# Octaplexerv6_1.net
KiCad netlist of a schematic drawn in EAGLE
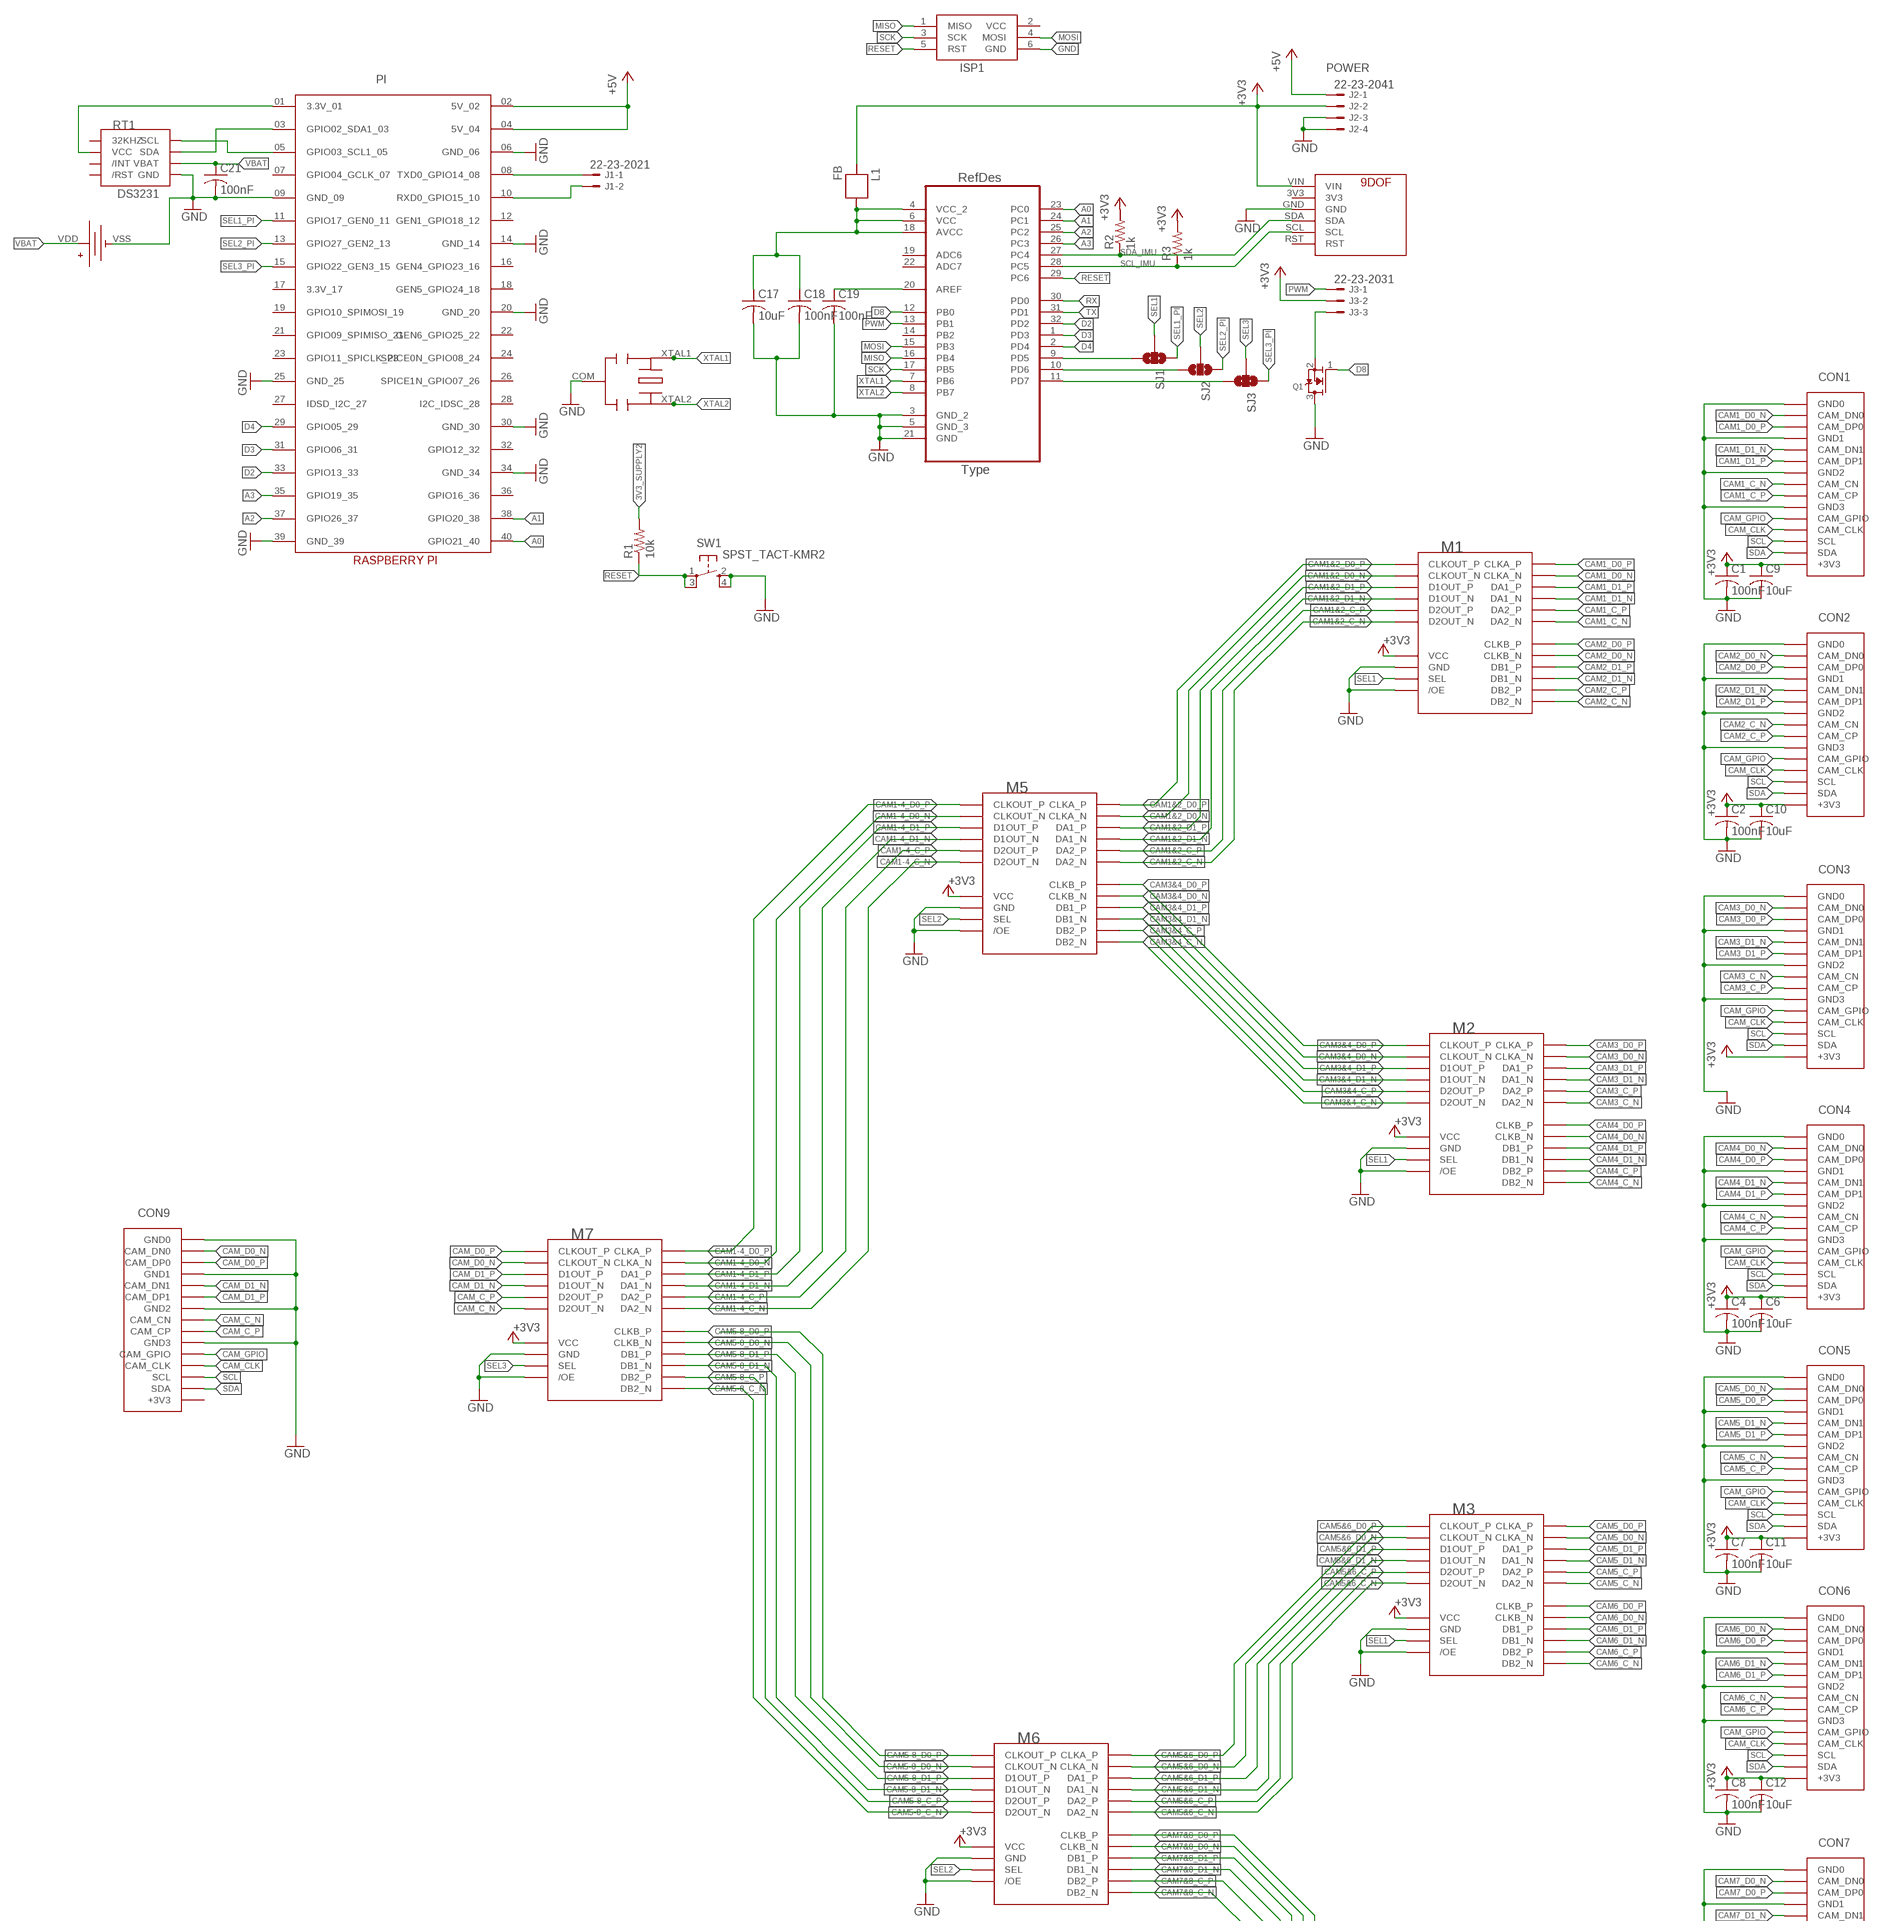
[diagram p0: schematic, sheet 1, part 1 of 2]
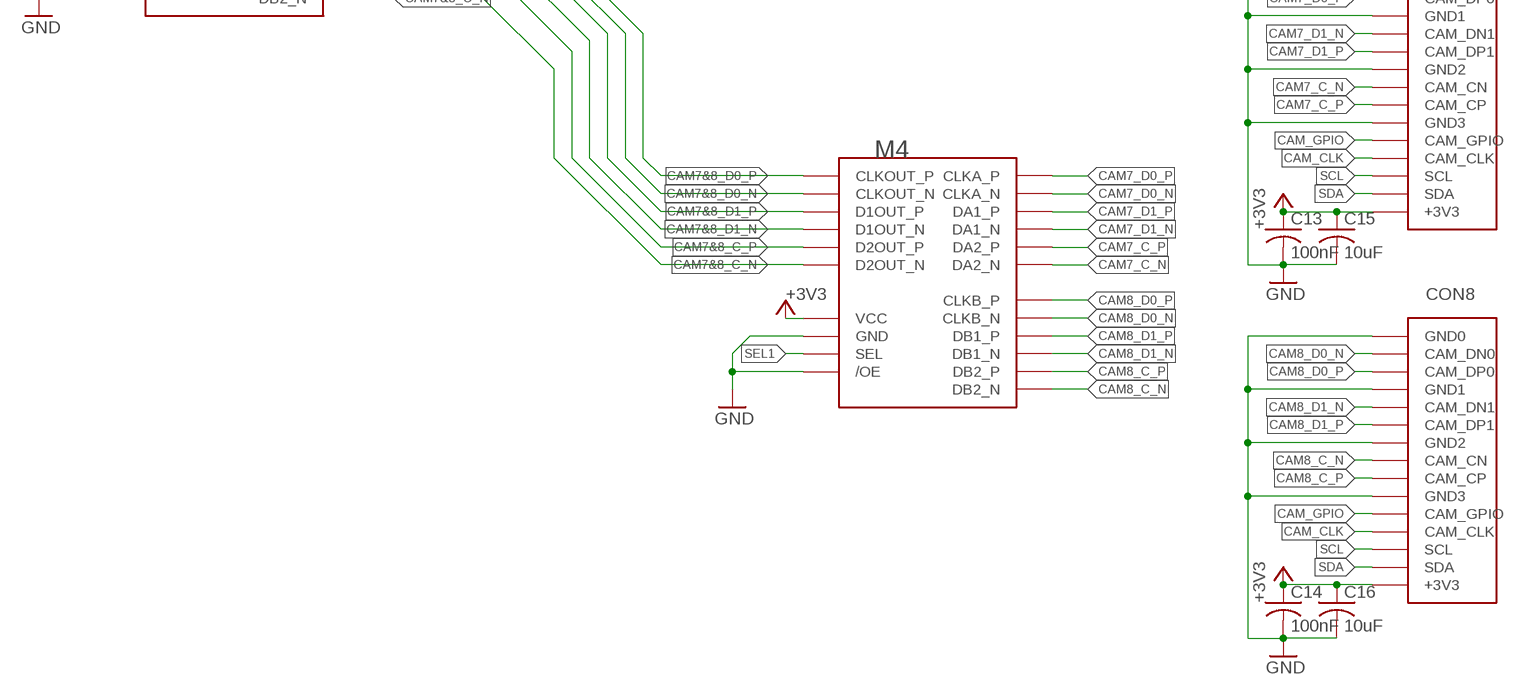
[diagram p1: schematic, sheet 1, part 2 of 2]

(export (version "E")
  (design (tool "Eeschema 10.0.6"))
  (components
    (comp (ref "C1")
      (value "100nF")
      (footprint "eagle-import:C0603")
      (libsource (lib "eagle-import") (part "C-USC0603"))
    )
    (comp (ref "C2")
      (value "100nF")
      (footprint "eagle-import:C0603")
      (libsource (lib "eagle-import") (part "C-USC0603"))
    )
    (comp (ref "C4")
      (value "100nF")
      (footprint "eagle-import:C0603")
      (libsource (lib "eagle-import") (part "C-USC0603"))
    )
    (comp (ref "C6")
      (value "10uF")
      (footprint "eagle-import:C0603")
      (libsource (lib "eagle-import") (part "C-USC0603"))
    )
    (comp (ref "C7")
      (value "100nF")
      (footprint "eagle-import:C0603")
      (libsource (lib "eagle-import") (part "C-USC0603"))
    )
    (comp (ref "C8")
      (value "100nF")
      (footprint "eagle-import:C0603")
      (libsource (lib "eagle-import") (part "C-USC0603"))
    )
    (comp (ref "C9")
      (value "10uF")
      (footprint "eagle-import:C0603")
      (libsource (lib "eagle-import") (part "C-USC0603"))
    )
    (comp (ref "C10")
      (value "10uF")
      (footprint "eagle-import:C0603")
      (libsource (lib "eagle-import") (part "C-USC0603"))
    )
    (comp (ref "C11")
      (value "10uF")
      (footprint "eagle-import:C0603")
      (libsource (lib "eagle-import") (part "C-USC0603"))
    )
    (comp (ref "C12")
      (value "10uF")
      (footprint "eagle-import:C0603")
      (libsource (lib "eagle-import") (part "C-USC0603"))
    )
    (comp (ref "C13")
      (value "100nF")
      (footprint "eagle-import:C0603")
      (libsource (lib "eagle-import") (part "C-USC0603"))
    )
    (comp (ref "C14")
      (value "100nF")
      (footprint "eagle-import:C0603")
      (libsource (lib "eagle-import") (part "C-USC0603"))
    )
    (comp (ref "C15")
      (value "10uF")
      (footprint "eagle-import:C0603")
      (libsource (lib "eagle-import") (part "C-USC0603"))
    )
    (comp (ref "C16")
      (value "10uF")
      (footprint "eagle-import:C0603")
      (libsource (lib "eagle-import") (part "C-USC0603"))
    )
    (comp (ref "C17")
      (value "10uF")
      (footprint "eagle-import:C0603")
      (libsource (lib "eagle-import") (part "C-USC0603"))
    )
    (comp (ref "C18")
      (value "100nF")
      (footprint "eagle-import:C0603")
      (libsource (lib "eagle-import") (part "C-USC0603"))
    )
    (comp (ref "C19")
      (value "100nF")
      (footprint "eagle-import:C0603")
      (libsource (lib "eagle-import") (part "C-USC0603"))
    )
    (comp (ref "C21")
      (value "100nF")
      (footprint "eagle-import:C0603")
      (libsource (lib "eagle-import") (part "C-USC0603"))
    )
    (comp (ref "CON1")
      (value "SLW15S-1C7LF")
      (footprint "eagle-import:SLW15R-1C7LF")
      (libsource (lib "eagle-import") (part "SLW15S-1C7LF"))
    )
    (comp (ref "CON2")
      (value "SLW15S-1C7LF")
      (footprint "eagle-import:SLW15R-1C7LF")
      (libsource (lib "eagle-import") (part "SLW15S-1C7LF"))
    )
    (comp (ref "CON3")
      (value "SLW15S-1C7LF")
      (footprint "eagle-import:SLW15R-1C7LF")
      (libsource (lib "eagle-import") (part "SLW15S-1C7LF"))
    )
    (comp (ref "CON4")
      (value "SLW15S-1C7LF")
      (footprint "eagle-import:SLW15R-1C7LF")
      (libsource (lib "eagle-import") (part "SLW15S-1C7LF"))
    )
    (comp (ref "CON5")
      (value "SLW15S-1C7LF")
      (footprint "eagle-import:SLW15R-1C7LF")
      (libsource (lib "eagle-import") (part "SLW15S-1C7LF"))
    )
    (comp (ref "CON6")
      (value "SLW15S-1C7LF")
      (footprint "eagle-import:SLW15R-1C7LF")
      (libsource (lib "eagle-import") (part "SLW15S-1C7LF"))
    )
    (comp (ref "CON7")
      (value "SLW15S-1C7LF")
      (footprint "eagle-import:SLW15R-1C7LF")
      (libsource (lib "eagle-import") (part "SLW15S-1C7LF"))
    )
    (comp (ref "CON8")
      (value "SLW15S-1C7LF")
      (footprint "eagle-import:SLW15R-1C7LF")
      (libsource (lib "eagle-import") (part "SLW15S-1C7LF"))
    )
    (comp (ref "CON9")
      (value "SLW15S-1C7LF")
      (footprint "eagle-import:SLW15R-1C7LF")
      (libsource (lib "eagle-import") (part "SLW15S-1C7LF"))
    )
    (comp (ref "ISP1")
      (value "AVRISP-6")
      (footprint "eagle-import:AVRISP")
      (libsource (lib "eagle-import") (part "AVRISP-6"))
    )
    (comp (ref "J1")
      (value "22-23-2021")
      (footprint "eagle-import:22-23-2021")
      (fields (field (name "MF") "MOLEX"))
      (libsource (lib "eagle-import") (part "22-23-2021"))
    )
    (comp (ref "J2")
      (value "22-23-2041")
      (footprint "eagle-import:22-23-2041")
      (fields (field (name "MF") "MOLEX"))
      (libsource (lib "eagle-import") (part "22-23-2041"))
    )
    (comp (ref "J3")
      (value "22-23-2031")
      (footprint "eagle-import:22-23-2031")
      (fields (field (name "MF") "MOLEX"))
      (libsource (lib "eagle-import") (part "22-23-2031"))
    )
    (comp (ref "L1")
      (value "FB")
      (footprint "eagle-import:0603")
      (libsource (lib "eagle-import") (part "FB"))
    )
    (comp (ref "M1")
      (value "FSA642")
      (footprint "eagle-import:FSA642")
      (libsource (lib "eagle-import") (part "FSA642"))
    )
    (comp (ref "M2")
      (value "FSA642")
      (footprint "eagle-import:FSA642")
      (libsource (lib "eagle-import") (part "FSA642"))
    )
    (comp (ref "M3")
      (value "FSA642")
      (footprint "eagle-import:FSA642")
      (libsource (lib "eagle-import") (part "FSA642"))
    )
    (comp (ref "M4")
      (value "FSA642")
      (footprint "eagle-import:FSA642")
      (libsource (lib "eagle-import") (part "FSA642"))
    )
    (comp (ref "M5")
      (value "FSA642")
      (footprint "eagle-import:FSA642")
      (libsource (lib "eagle-import") (part "FSA642"))
    )
    (comp (ref "M6")
      (value "FSA642")
      (footprint "eagle-import:FSA642")
      (libsource (lib "eagle-import") (part "FSA642"))
    )
    (comp (ref "M7")
      (value "FSA642")
      (footprint "eagle-import:FSA642")
      (libsource (lib "eagle-import") (part "FSA642"))
    )
    (comp (ref "PI")
      (value "RASPBERRYPI_SHIELD")
      (footprint "eagle-import:RASPBERRYPI_SHIELD")
      (libsource (lib "eagle-import") (part "RASPBERRYPI_SHIELD"))
    )
    (comp (ref "Q1")
      (value "MOSFET-NREFLOW")
      (footprint "eagle-import:SOT23")
      (libsource (lib "eagle-import") (part "MOSFET-NREFLOW"))
    )
    (comp (ref "R1")
      (value "10k")
      (footprint "eagle-import:R0603")
      (libsource (lib "eagle-import") (part "R-US_R0603"))
    )
    (comp (ref "R2")
      (value "1k")
      (footprint "eagle-import:R0603")
      (libsource (lib "eagle-import") (part "R-US_R0603"))
    )
    (comp (ref "R3")
      (value "1k")
      (footprint "eagle-import:R0603")
      (libsource (lib "eagle-import") (part "R-US_R0603"))
    )
    (comp (ref "RT1")
      (value "DS3231M")
      (footprint "eagle-import:SO-8")
      (libsource (lib "eagle-import") (part "DS3231M"))
    )
    (comp (ref "S1")
      (value "CR-1220/HFN")
      (footprint "eagle-import:CR-1220_HFN")
      (libsource (lib "eagle-import") (part "CR-1220/HFN"))
    )
    (comp (ref "SJ1")
      (value "SOLDERJUMPER_2WAYPASTE2&3")
      (footprint "eagle-import:SJ_3_PASTE2&3")
      (libsource (lib "eagle-import") (part "SOLDERJUMPER_2WAYPASTE2&3"))
    )
    (comp (ref "SJ2")
      (value "SOLDERJUMPER_2WAYPASTE2&3")
      (footprint "eagle-import:SJ_3_PASTE2&3")
      (libsource (lib "eagle-import") (part "SOLDERJUMPER_2WAYPASTE2&3"))
    )
    (comp (ref "SJ3")
      (value "SOLDERJUMPER_2WAYPASTE2&3")
      (footprint "eagle-import:SJ_3_PASTE2&3")
      (libsource (lib "eagle-import") (part "SOLDERJUMPER_2WAYPASTE2&3"))
    )
    (comp (ref "SW1")
      (value "SPST_TACT-KMR2")
      (footprint "eagle-import:KMR2")
      (libsource (lib "eagle-import") (part "SPST_TACT-KMR2"))
    )
    (comp (ref "U$2")
      (value "9DOF-BNO055")
      (footprint "eagle-import:9DOF_FLAT")
      (libsource (lib "eagle-import") (part "9DOF-BNO055"))
    )
    (comp (ref "U1")
      (value "ATMEGA328P-AU")
      (footprint "eagle-import:QFP80P900X900X120-32N")
      (libsource (lib "eagle-import") (part "ATMEGA328P-AU"))
    )
    (comp (ref "X1")
      (value "RESONATOR-PRQC")
      (footprint "eagle-import:PRQC")
      (libsource (lib "eagle-import") (part "RESONATOR-PRQC"))
    )
  )
  (nets
    (net (code "1") (name "+3V3") (class "Default")
      (node (ref "C1") (pin "1") (pinfunction "1_1") (pintype "passive"))
      (node (ref "C10") (pin "1") (pinfunction "1_1") (pintype "passive"))
      (node (ref "C11") (pin "1") (pinfunction "1_1") (pintype "passive"))
      (node (ref "C12") (pin "1") (pinfunction "1_1") (pintype "passive"))
      (node (ref "C13") (pin "1") (pinfunction "1_1") (pintype "passive"))
      (node (ref "C14") (pin "1") (pinfunction "1_1") (pintype "passive"))
      (node (ref "C15") (pin "1") (pinfunction "1_1") (pintype "passive"))
      (node (ref "C16") (pin "1") (pinfunction "1_1") (pintype "passive"))
      (node (ref "C2") (pin "1") (pinfunction "1_1") (pintype "passive"))
      (node (ref "C4") (pin "1") (pinfunction "1_1") (pintype "passive"))
      (node (ref "C6") (pin "1") (pinfunction "1_1") (pintype "passive"))
      (node (ref "C7") (pin "1") (pinfunction "1_1") (pintype "passive"))
      (node (ref "C8") (pin "1") (pinfunction "1_1") (pintype "passive"))
      (node (ref "C9") (pin "1") (pinfunction "1_1") (pintype "passive"))
      (node (ref "CON1") (pin "3.3V") (pinfunction "+3V3_3.3V") (pintype "bidirectional"))
      (node (ref "CON2") (pin "3.3V") (pinfunction "+3V3_3.3V") (pintype "bidirectional"))
      (node (ref "CON3") (pin "3.3V") (pinfunction "+3V3_3.3V") (pintype "bidirectional"))
      (node (ref "CON4") (pin "3.3V") (pinfunction "+3V3_3.3V") (pintype "bidirectional"))
      (node (ref "CON5") (pin "3.3V") (pinfunction "+3V3_3.3V") (pintype "bidirectional"))
      (node (ref "CON6") (pin "3.3V") (pinfunction "+3V3_3.3V") (pintype "bidirectional"))
      (node (ref "CON7") (pin "3.3V") (pinfunction "+3V3_3.3V") (pintype "bidirectional"))
      (node (ref "CON8") (pin "3.3V") (pinfunction "+3V3_3.3V") (pintype "bidirectional"))
      (node (ref "J2") (pin "2") (pinfunction "S_2") (pintype "passive"))
      (node (ref "J3") (pin "2") (pinfunction "S_2") (pintype "passive"))
      (node (ref "L1") (pin "2") (pinfunction "P$2_2") (pintype "bidirectional"))
      (node (ref "M1") (pin "VCC") (pinfunction "VCC_VCC") (pintype "bidirectional"))
      (node (ref "M2") (pin "VCC") (pinfunction "VCC_VCC") (pintype "bidirectional"))
      (node (ref "M3") (pin "VCC") (pinfunction "VCC_VCC") (pintype "bidirectional"))
      (node (ref "M4") (pin "VCC") (pinfunction "VCC_VCC") (pintype "bidirectional"))
      (node (ref "M5") (pin "VCC") (pinfunction "VCC_VCC") (pintype "bidirectional"))
      (node (ref "M6") (pin "VCC") (pinfunction "VCC_VCC") (pintype "bidirectional"))
      (node (ref "M7") (pin "VCC") (pinfunction "VCC_VCC") (pintype "bidirectional"))
      (node (ref "R2") (pin "2") (pinfunction "2_2") (pintype "passive"))
      (node (ref "R3") (pin "2") (pinfunction "2_2") (pintype "passive"))
      (node (ref "U$2") (pin "VIN") (pinfunction "VIN_VIN") (pintype "bidirectional"))
    )
    (net (code "2") (name "+5V") (class "Default")
      (node (ref "J2") (pin "1") (pinfunction "S_1") (pintype "passive"))
      (node (ref "PI") (pin "02") (pinfunction "5V_02_02") (pintype "bidirectional"))
      (node (ref "PI") (pin "04") (pinfunction "5V_04_04") (pintype "bidirectional"))
    )
    (net (code "3") (name "/SCL_IMU") (class "Default")
      (node (ref "R3") (pin "1") (pinfunction "1_1") (pintype "passive"))
      (node (ref "U$2") (pin "SCL") (pinfunction "SCL_SCL") (pintype "bidirectional"))
      (node (ref "U1") (pin "28") (pinfunction "PC5_28") (pintype "bidirectional"))
    )
    (net (code "4") (name "/SDA_IMU") (class "Default")
      (node (ref "R2") (pin "1") (pinfunction "1_1") (pintype "passive"))
      (node (ref "U$2") (pin "SDA") (pinfunction "SDA_SDA") (pintype "bidirectional"))
      (node (ref "U1") (pin "27") (pinfunction "PC4_27") (pintype "bidirectional"))
    )
    (net (code "5") (name "/VCC") (class "Default")
      (node (ref "ISP1") (pin "2") (pinfunction "VCC_2") (pintype "power_in"))
    )
    (net (code "6") (name "3V3_SUPPLY2") (class "Default")
      (node (ref "C17") (pin "1") (pinfunction "1_1") (pintype "passive"))
      (node (ref "C18") (pin "1") (pinfunction "1_1") (pintype "passive"))
      (node (ref "L1") (pin "1") (pinfunction "P$1_1") (pintype "bidirectional"))
      (node (ref "R1") (pin "2") (pinfunction "2_2") (pintype "passive"))
      (node (ref "U1") (pin "18") (pinfunction "AVCC_18") (pintype "power_in"))
      (node (ref "U1") (pin "4") (pinfunction "VCC_2_4") (pintype "power_in"))
      (node (ref "U1") (pin "6") (pinfunction "VCC_6") (pintype "power_in"))
    )
    (net (code "7") (name "A0") (class "Default")
      (node (ref "PI") (pin "40") (pinfunction "GPIO21_40_40") (pintype "bidirectional"))
      (node (ref "U1") (pin "23") (pinfunction "PC0_23") (pintype "bidirectional"))
    )
    (net (code "8") (name "A1") (class "Default")
      (node (ref "PI") (pin "38") (pinfunction "GPIO20_38_38") (pintype "bidirectional"))
      (node (ref "U1") (pin "24") (pinfunction "PC1_24") (pintype "bidirectional"))
    )
    (net (code "9") (name "A2") (class "Default")
      (node (ref "PI") (pin "37") (pinfunction "GPIO26_37_37") (pintype "bidirectional"))
      (node (ref "U1") (pin "25") (pinfunction "PC2_25") (pintype "bidirectional"))
    )
    (net (code "10") (name "A3") (class "Default")
      (node (ref "PI") (pin "35") (pinfunction "GPIO19_35_35") (pintype "bidirectional"))
      (node (ref "U1") (pin "26") (pinfunction "PC3_26") (pintype "bidirectional"))
    )
    (net (code "11") (name "CAM1&2_C_N") (class "Default")
      (node (ref "M1") (pin "D2N") (pinfunction "D2OUT_N_D2N") (pintype "bidirectional"))
      (node (ref "M5") (pin "DA2N") (pinfunction "DA2_N_DA2N") (pintype "bidirectional"))
    )
    (net (code "12") (name "CAM1&2_C_P") (class "Default")
      (node (ref "M1") (pin "D2P") (pinfunction "D2OUT_P_D2P") (pintype "bidirectional"))
      (node (ref "M5") (pin "DA2P") (pinfunction "DA2_P_DA2P") (pintype "bidirectional"))
    )
    (net (code "13") (name "CAM1&2_D0_N") (class "Default")
      (node (ref "M1") (pin "CLKN") (pinfunction "CLKOUT_N_CLKN") (pintype "bidirectional"))
      (node (ref "M5") (pin "CLKAN") (pinfunction "CLKA_N_CLKAN") (pintype "bidirectional"))
    )
    (net (code "14") (name "CAM1&2_D0_P") (class "Default")
      (node (ref "M1") (pin "CLKP") (pinfunction "CLKOUT_P_CLKP") (pintype "bidirectional"))
      (node (ref "M5") (pin "CLKAP") (pinfunction "CLKA_P_CLKAP") (pintype "bidirectional"))
    )
    (net (code "15") (name "CAM1&2_D1_N") (class "Default")
      (node (ref "M1") (pin "D1N") (pinfunction "D1OUT_N_D1N") (pintype "bidirectional"))
      (node (ref "M5") (pin "DA1N") (pinfunction "DA1_N_DA1N") (pintype "bidirectional"))
    )
    (net (code "16") (name "CAM1&2_D1_P") (class "Default")
      (node (ref "M1") (pin "D1P") (pinfunction "D1OUT_P_D1P") (pintype "bidirectional"))
      (node (ref "M5") (pin "DA1P") (pinfunction "DA1_P_DA1P") (pintype "bidirectional"))
    )
    (net (code "17") (name "CAM1-4_C_N") (class "Default")
      (node (ref "M5") (pin "D2N") (pinfunction "D2OUT_N_D2N") (pintype "bidirectional"))
      (node (ref "M7") (pin "DA2N") (pinfunction "DA2_N_DA2N") (pintype "bidirectional"))
    )
    (net (code "18") (name "CAM1-4_C_P") (class "Default")
      (node (ref "M5") (pin "D2P") (pinfunction "D2OUT_P_D2P") (pintype "bidirectional"))
      (node (ref "M7") (pin "DA2P") (pinfunction "DA2_P_DA2P") (pintype "bidirectional"))
    )
    (net (code "19") (name "CAM1-4_D0_N") (class "Default")
      (node (ref "M5") (pin "CLKN") (pinfunction "CLKOUT_N_CLKN") (pintype "bidirectional"))
      (node (ref "M7") (pin "CLKAN") (pinfunction "CLKA_N_CLKAN") (pintype "bidirectional"))
    )
    (net (code "20") (name "CAM1-4_D0_P") (class "Default")
      (node (ref "M5") (pin "CLKP") (pinfunction "CLKOUT_P_CLKP") (pintype "bidirectional"))
      (node (ref "M7") (pin "CLKAP") (pinfunction "CLKA_P_CLKAP") (pintype "bidirectional"))
    )
    (net (code "21") (name "CAM1-4_D1_N") (class "Default")
      (node (ref "M5") (pin "D1N") (pinfunction "D1OUT_N_D1N") (pintype "bidirectional"))
      (node (ref "M7") (pin "DA1N") (pinfunction "DA1_N_DA1N") (pintype "bidirectional"))
    )
    (net (code "22") (name "CAM1-4_D1_P") (class "Default")
      (node (ref "M5") (pin "D1P") (pinfunction "D1OUT_P_D1P") (pintype "bidirectional"))
      (node (ref "M7") (pin "DA1P") (pinfunction "DA1_P_DA1P") (pintype "bidirectional"))
    )
    (net (code "23") (name "CAM1_C_N") (class "Default")
      (node (ref "CON1") (pin "CAM_C_N") (pinfunction "CAM_CN_CAM_C_N") (pintype "bidirectional"))
      (node (ref "M1") (pin "DA2N") (pinfunction "DA2_N_DA2N") (pintype "bidirectional"))
    )
    (net (code "24") (name "CAM1_C_P") (class "Default")
      (node (ref "CON1") (pin "CAM_C_P") (pinfunction "CAM_CP_CAM_C_P") (pintype "bidirectional"))
      (node (ref "M1") (pin "DA2P") (pinfunction "DA2_P_DA2P") (pintype "bidirectional"))
    )
    (net (code "25") (name "CAM1_D0_N") (class "Default")
      (node (ref "CON1") (pin "CAM_D0_N") (pinfunction "CAM_DN0_CAM_D0_N") (pintype "bidirectional"))
      (node (ref "M1") (pin "CLKAN") (pinfunction "CLKA_N_CLKAN") (pintype "bidirectional"))
    )
    (net (code "26") (name "CAM1_D0_P") (class "Default")
      (node (ref "CON1") (pin "CAM_D0_P") (pinfunction "CAM_DP0_CAM_D0_P") (pintype "bidirectional"))
      (node (ref "M1") (pin "CLKAP") (pinfunction "CLKA_P_CLKAP") (pintype "bidirectional"))
    )
    (net (code "27") (name "CAM1_D1_N") (class "Default")
      (node (ref "CON1") (pin "CAM_D1_N") (pinfunction "CAM_DN1_CAM_D1_N") (pintype "bidirectional"))
      (node (ref "M1") (pin "DA1N") (pinfunction "DA1_N_DA1N") (pintype "bidirectional"))
    )
    (net (code "28") (name "CAM1_D1_P") (class "Default")
      (node (ref "CON1") (pin "CAM_D1_P") (pinfunction "CAM_DP1_CAM_D1_P") (pintype "bidirectional"))
      (node (ref "M1") (pin "DA1P") (pinfunction "DA1_P_DA1P") (pintype "bidirectional"))
    )
    (net (code "29") (name "CAM2_C_N") (class "Default")
      (node (ref "CON2") (pin "CAM_C_N") (pinfunction "CAM_CN_CAM_C_N") (pintype "bidirectional"))
      (node (ref "M1") (pin "DB2N") (pinfunction "DB2_N_DB2N") (pintype "bidirectional"))
    )
    (net (code "30") (name "CAM2_C_P") (class "Default")
      (node (ref "CON2") (pin "CAM_C_P") (pinfunction "CAM_CP_CAM_C_P") (pintype "bidirectional"))
      (node (ref "M1") (pin "DB2P") (pinfunction "DB2_P_DB2P") (pintype "bidirectional"))
    )
    (net (code "31") (name "CAM2_D0_N") (class "Default")
      (node (ref "CON2") (pin "CAM_D0_N") (pinfunction "CAM_DN0_CAM_D0_N") (pintype "bidirectional"))
      (node (ref "M1") (pin "CLKBN") (pinfunction "CLKB_N_CLKBN") (pintype "bidirectional"))
    )
    (net (code "32") (name "CAM2_D0_P") (class "Default")
      (node (ref "CON2") (pin "CAM_D0_P") (pinfunction "CAM_DP0_CAM_D0_P") (pintype "bidirectional"))
      (node (ref "M1") (pin "CLKBP") (pinfunction "CLKB_P_CLKBP") (pintype "bidirectional"))
    )
    (net (code "33") (name "CAM2_D1_N") (class "Default")
      (node (ref "CON2") (pin "CAM_D1_N") (pinfunction "CAM_DN1_CAM_D1_N") (pintype "bidirectional"))
      (node (ref "M1") (pin "DB1N") (pinfunction "DB1_N_DB1N") (pintype "bidirectional"))
    )
    (net (code "34") (name "CAM2_D1_P") (class "Default")
      (node (ref "CON2") (pin "CAM_D1_P") (pinfunction "CAM_DP1_CAM_D1_P") (pintype "bidirectional"))
      (node (ref "M1") (pin "DB1P") (pinfunction "DB1_P_DB1P") (pintype "bidirectional"))
    )
    (net (code "35") (name "CAM3&4_C_N") (class "Default")
      (node (ref "M2") (pin "D2N") (pinfunction "D2OUT_N_D2N") (pintype "bidirectional"))
      (node (ref "M5") (pin "DB2N") (pinfunction "DB2_N_DB2N") (pintype "bidirectional"))
    )
    (net (code "36") (name "CAM3&4_C_P") (class "Default")
      (node (ref "M2") (pin "D2P") (pinfunction "D2OUT_P_D2P") (pintype "bidirectional"))
      (node (ref "M5") (pin "DB2P") (pinfunction "DB2_P_DB2P") (pintype "bidirectional"))
    )
    (net (code "37") (name "CAM3&4_D0_N") (class "Default")
      (node (ref "M2") (pin "CLKN") (pinfunction "CLKOUT_N_CLKN") (pintype "bidirectional"))
      (node (ref "M5") (pin "CLKBN") (pinfunction "CLKB_N_CLKBN") (pintype "bidirectional"))
    )
    (net (code "38") (name "CAM3&4_D0_P") (class "Default")
      (node (ref "M2") (pin "CLKP") (pinfunction "CLKOUT_P_CLKP") (pintype "bidirectional"))
      (node (ref "M5") (pin "CLKBP") (pinfunction "CLKB_P_CLKBP") (pintype "bidirectional"))
    )
    (net (code "39") (name "CAM3&4_D1_N") (class "Default")
      (node (ref "M2") (pin "D1N") (pinfunction "D1OUT_N_D1N") (pintype "bidirectional"))
      (node (ref "M5") (pin "DB1N") (pinfunction "DB1_N_DB1N") (pintype "bidirectional"))
    )
    (net (code "40") (name "CAM3&4_D1_P") (class "Default")
      (node (ref "M2") (pin "D1P") (pinfunction "D1OUT_P_D1P") (pintype "bidirectional"))
      (node (ref "M5") (pin "DB1P") (pinfunction "DB1_P_DB1P") (pintype "bidirectional"))
    )
    (net (code "41") (name "CAM3_C_N") (class "Default")
      (node (ref "CON3") (pin "CAM_C_N") (pinfunction "CAM_CN_CAM_C_N") (pintype "bidirectional"))
      (node (ref "M2") (pin "DA2N") (pinfunction "DA2_N_DA2N") (pintype "bidirectional"))
    )
    (net (code "42") (name "CAM3_C_P") (class "Default")
      (node (ref "CON3") (pin "CAM_C_P") (pinfunction "CAM_CP_CAM_C_P") (pintype "bidirectional"))
      (node (ref "M2") (pin "DA2P") (pinfunction "DA2_P_DA2P") (pintype "bidirectional"))
    )
    (net (code "43") (name "CAM3_D0_N") (class "Default")
      (node (ref "CON3") (pin "CAM_D0_N") (pinfunction "CAM_DN0_CAM_D0_N") (pintype "bidirectional"))
      (node (ref "M2") (pin "CLKAN") (pinfunction "CLKA_N_CLKAN") (pintype "bidirectional"))
    )
    (net (code "44") (name "CAM3_D0_P") (class "Default")
      (node (ref "CON3") (pin "CAM_D0_P") (pinfunction "CAM_DP0_CAM_D0_P") (pintype "bidirectional"))
      (node (ref "M2") (pin "CLKAP") (pinfunction "CLKA_P_CLKAP") (pintype "bidirectional"))
    )
    (net (code "45") (name "CAM3_D1_N") (class "Default")
      (node (ref "CON3") (pin "CAM_D1_N") (pinfunction "CAM_DN1_CAM_D1_N") (pintype "bidirectional"))
      (node (ref "M2") (pin "DA1N") (pinfunction "DA1_N_DA1N") (pintype "bidirectional"))
    )
    (net (code "46") (name "CAM3_D1_P") (class "Default")
      (node (ref "CON3") (pin "CAM_D1_P") (pinfunction "CAM_DP1_CAM_D1_P") (pintype "bidirectional"))
      (node (ref "M2") (pin "DA1P") (pinfunction "DA1_P_DA1P") (pintype "bidirectional"))
    )
    (net (code "47") (name "CAM4_C_N") (class "Default")
      (node (ref "CON4") (pin "CAM_C_N") (pinfunction "CAM_CN_CAM_C_N") (pintype "bidirectional"))
      (node (ref "M2") (pin "DB2N") (pinfunction "DB2_N_DB2N") (pintype "bidirectional"))
    )
    (net (code "48") (name "CAM4_C_P") (class "Default")
      (node (ref "CON4") (pin "CAM_C_P") (pinfunction "CAM_CP_CAM_C_P") (pintype "bidirectional"))
      (node (ref "M2") (pin "DB2P") (pinfunction "DB2_P_DB2P") (pintype "bidirectional"))
    )
    (net (code "49") (name "CAM4_D0_N") (class "Default")
      (node (ref "CON4") (pin "CAM_D0_N") (pinfunction "CAM_DN0_CAM_D0_N") (pintype "bidirectional"))
      (node (ref "M2") (pin "CLKBN") (pinfunction "CLKB_N_CLKBN") (pintype "bidirectional"))
    )
    (net (code "50") (name "CAM4_D0_P") (class "Default")
      (node (ref "CON4") (pin "CAM_D0_P") (pinfunction "CAM_DP0_CAM_D0_P") (pintype "bidirectional"))
      (node (ref "M2") (pin "CLKBP") (pinfunction "CLKB_P_CLKBP") (pintype "bidirectional"))
    )
    (net (code "51") (name "CAM4_D1_N") (class "Default")
      (node (ref "CON4") (pin "CAM_D1_N") (pinfunction "CAM_DN1_CAM_D1_N") (pintype "bidirectional"))
      (node (ref "M2") (pin "DB1N") (pinfunction "DB1_N_DB1N") (pintype "bidirectional"))
    )
    (net (code "52") (name "CAM4_D1_P") (class "Default")
      (node (ref "CON4") (pin "CAM_D1_P") (pinfunction "CAM_DP1_CAM_D1_P") (pintype "bidirectional"))
      (node (ref "M2") (pin "DB1P") (pinfunction "DB1_P_DB1P") (pintype "bidirectional"))
    )
    (net (code "53") (name "CAM5&6_C_N") (class "Default")
      (node (ref "M3") (pin "D2N") (pinfunction "D2OUT_N_D2N") (pintype "bidirectional"))
      (node (ref "M6") (pin "DA2N") (pinfunction "DA2_N_DA2N") (pintype "bidirectional"))
    )
    (net (code "54") (name "CAM5&6_C_P") (class "Default")
      (node (ref "M3") (pin "D2P") (pinfunction "D2OUT_P_D2P") (pintype "bidirectional"))
      (node (ref "M6") (pin "DA2P") (pinfunction "DA2_P_DA2P") (pintype "bidirectional"))
    )
    (net (code "55") (name "CAM5&6_D0_N") (class "Default")
      (node (ref "M3") (pin "CLKN") (pinfunction "CLKOUT_N_CLKN") (pintype "bidirectional"))
      (node (ref "M6") (pin "CLKAN") (pinfunction "CLKA_N_CLKAN") (pintype "bidirectional"))
    )
    (net (code "56") (name "CAM5&6_D0_P") (class "Default")
      (node (ref "M3") (pin "CLKP") (pinfunction "CLKOUT_P_CLKP") (pintype "bidirectional"))
      (node (ref "M6") (pin "CLKAP") (pinfunction "CLKA_P_CLKAP") (pintype "bidirectional"))
    )
    (net (code "57") (name "CAM5&6_D1_N") (class "Default")
      (node (ref "M3") (pin "D1N") (pinfunction "D1OUT_N_D1N") (pintype "bidirectional"))
      (node (ref "M6") (pin "DA1N") (pinfunction "DA1_N_DA1N") (pintype "bidirectional"))
    )
    (net (code "58") (name "CAM5&6_D1_P") (class "Default")
      (node (ref "M3") (pin "D1P") (pinfunction "D1OUT_P_D1P") (pintype "bidirectional"))
      (node (ref "M6") (pin "DA1P") (pinfunction "DA1_P_DA1P") (pintype "bidirectional"))
    )
    (net (code "59") (name "CAM5-8_C_N") (class "Default")
      (node (ref "M6") (pin "D2N") (pinfunction "D2OUT_N_D2N") (pintype "bidirectional"))
      (node (ref "M7") (pin "DB2N") (pinfunction "DB2_N_DB2N") (pintype "bidirectional"))
    )
    (net (code "60") (name "CAM5-8_C_P") (class "Default")
      (node (ref "M6") (pin "D2P") (pinfunction "D2OUT_P_D2P") (pintype "bidirectional"))
      (node (ref "M7") (pin "DB2P") (pinfunction "DB2_P_DB2P") (pintype "bidirectional"))
    )
    (net (code "61") (name "CAM5-8_D0_N") (class "Default")
      (node (ref "M6") (pin "CLKN") (pinfunction "CLKOUT_N_CLKN") (pintype "bidirectional"))
      (node (ref "M7") (pin "CLKBN") (pinfunction "CLKB_N_CLKBN") (pintype "bidirectional"))
    )
    (net (code "62") (name "CAM5-8_D0_P") (class "Default")
      (node (ref "M6") (pin "CLKP") (pinfunction "CLKOUT_P_CLKP") (pintype "bidirectional"))
      (node (ref "M7") (pin "CLKBP") (pinfunction "CLKB_P_CLKBP") (pintype "bidirectional"))
    )
    (net (code "63") (name "CAM5-8_D1_N") (class "Default")
      (node (ref "M6") (pin "D1N") (pinfunction "D1OUT_N_D1N") (pintype "bidirectional"))
      (node (ref "M7") (pin "DB1N") (pinfunction "DB1_N_DB1N") (pintype "bidirectional"))
    )
    (net (code "64") (name "CAM5-8_D1_P") (class "Default")
      (node (ref "M6") (pin "D1P") (pinfunction "D1OUT_P_D1P") (pintype "bidirectional"))
      (node (ref "M7") (pin "DB1P") (pinfunction "DB1_P_DB1P") (pintype "bidirectional"))
    )
    (net (code "65") (name "CAM5_C_N") (class "Default")
      (node (ref "CON5") (pin "CAM_C_N") (pinfunction "CAM_CN_CAM_C_N") (pintype "bidirectional"))
      (node (ref "M3") (pin "DA2N") (pinfunction "DA2_N_DA2N") (pintype "bidirectional"))
    )
    (net (code "66") (name "CAM5_C_P") (class "Default")
      (node (ref "CON5") (pin "CAM_C_P") (pinfunction "CAM_CP_CAM_C_P") (pintype "bidirectional"))
      (node (ref "M3") (pin "DA2P") (pinfunction "DA2_P_DA2P") (pintype "bidirectional"))
    )
    (net (code "67") (name "CAM5_D0_N") (class "Default")
      (node (ref "CON5") (pin "CAM_D0_N") (pinfunction "CAM_DN0_CAM_D0_N") (pintype "bidirectional"))
      (node (ref "M3") (pin "CLKAN") (pinfunction "CLKA_N_CLKAN") (pintype "bidirectional"))
    )
    (net (code "68") (name "CAM5_D0_P") (class "Default")
      (node (ref "CON5") (pin "CAM_D0_P") (pinfunction "CAM_DP0_CAM_D0_P") (pintype "bidirectional"))
      (node (ref "M3") (pin "CLKAP") (pinfunction "CLKA_P_CLKAP") (pintype "bidirectional"))
    )
    (net (code "69") (name "CAM5_D1_N") (class "Default")
      (node (ref "CON5") (pin "CAM_D1_N") (pinfunction "CAM_DN1_CAM_D1_N") (pintype "bidirectional"))
      (node (ref "M3") (pin "DA1N") (pinfunction "DA1_N_DA1N") (pintype "bidirectional"))
    )
    (net (code "70") (name "CAM5_D1_P") (class "Default")
      (node (ref "CON5") (pin "CAM_D1_P") (pinfunction "CAM_DP1_CAM_D1_P") (pintype "bidirectional"))
      (node (ref "M3") (pin "DA1P") (pinfunction "DA1_P_DA1P") (pintype "bidirectional"))
    )
    (net (code "71") (name "CAM6_C_N") (class "Default")
      (node (ref "CON6") (pin "CAM_C_N") (pinfunction "CAM_CN_CAM_C_N") (pintype "bidirectional"))
      (node (ref "M3") (pin "DB2N") (pinfunction "DB2_N_DB2N") (pintype "bidirectional"))
    )
    (net (code "72") (name "CAM6_C_P") (class "Default")
      (node (ref "CON6") (pin "CAM_C_P") (pinfunction "CAM_CP_CAM_C_P") (pintype "bidirectional"))
      (node (ref "M3") (pin "DB2P") (pinfunction "DB2_P_DB2P") (pintype "bidirectional"))
    )
    (net (code "73") (name "CAM6_D0_N") (class "Default")
      (node (ref "CON6") (pin "CAM_D0_N") (pinfunction "CAM_DN0_CAM_D0_N") (pintype "bidirectional"))
      (node (ref "M3") (pin "CLKBN") (pinfunction "CLKB_N_CLKBN") (pintype "bidirectional"))
    )
    (net (code "74") (name "CAM6_D0_P") (class "Default")
      (node (ref "CON6") (pin "CAM_D0_P") (pinfunction "CAM_DP0_CAM_D0_P") (pintype "bidirectional"))
      (node (ref "M3") (pin "CLKBP") (pinfunction "CLKB_P_CLKBP") (pintype "bidirectional"))
    )
    (net (code "75") (name "CAM6_D1_N") (class "Default")
      (node (ref "CON6") (pin "CAM_D1_N") (pinfunction "CAM_DN1_CAM_D1_N") (pintype "bidirectional"))
      (node (ref "M3") (pin "DB1N") (pinfunction "DB1_N_DB1N") (pintype "bidirectional"))
    )
    (net (code "76") (name "CAM6_D1_P") (class "Default")
      (node (ref "CON6") (pin "CAM_D1_P") (pinfunction "CAM_DP1_CAM_D1_P") (pintype "bidirectional"))
      (node (ref "M3") (pin "DB1P") (pinfunction "DB1_P_DB1P") (pintype "bidirectional"))
    )
    (net (code "77") (name "CAM7&8_C_N") (class "Default")
      (node (ref "M4") (pin "D2N") (pinfunction "D2OUT_N_D2N") (pintype "bidirectional"))
      (node (ref "M6") (pin "DB2N") (pinfunction "DB2_N_DB2N") (pintype "bidirectional"))
    )
    (net (code "78") (name "CAM7&8_C_P") (class "Default")
      (node (ref "M4") (pin "D2P") (pinfunction "D2OUT_P_D2P") (pintype "bidirectional"))
      (node (ref "M6") (pin "DB2P") (pinfunction "DB2_P_DB2P") (pintype "bidirectional"))
    )
    (net (code "79") (name "CAM7&8_D0_N") (class "Default")
      (node (ref "M4") (pin "CLKN") (pinfunction "CLKOUT_N_CLKN") (pintype "bidirectional"))
      (node (ref "M6") (pin "CLKBN") (pinfunction "CLKB_N_CLKBN") (pintype "bidirectional"))
    )
    (net (code "80") (name "CAM7&8_D0_P") (class "Default")
      (node (ref "M4") (pin "CLKP") (pinfunction "CLKOUT_P_CLKP") (pintype "bidirectional"))
      (node (ref "M6") (pin "CLKBP") (pinfunction "CLKB_P_CLKBP") (pintype "bidirectional"))
    )
    (net (code "81") (name "CAM7&8_D1_N") (class "Default")
      (node (ref "M4") (pin "D1N") (pinfunction "D1OUT_N_D1N") (pintype "bidirectional"))
      (node (ref "M6") (pin "DB1N") (pinfunction "DB1_N_DB1N") (pintype "bidirectional"))
    )
    (net (code "82") (name "CAM7&8_D1_P") (class "Default")
      (node (ref "M4") (pin "D1P") (pinfunction "D1OUT_P_D1P") (pintype "bidirectional"))
      (node (ref "M6") (pin "DB1P") (pinfunction "DB1_P_DB1P") (pintype "bidirectional"))
    )
    (net (code "83") (name "CAM7_C_N") (class "Default")
      (node (ref "CON7") (pin "CAM_C_N") (pinfunction "CAM_CN_CAM_C_N") (pintype "bidirectional"))
      (node (ref "M4") (pin "DA2N") (pinfunction "DA2_N_DA2N") (pintype "bidirectional"))
    )
    (net (code "84") (name "CAM7_C_P") (class "Default")
      (node (ref "CON7") (pin "CAM_C_P") (pinfunction "CAM_CP_CAM_C_P") (pintype "bidirectional"))
      (node (ref "M4") (pin "DA2P") (pinfunction "DA2_P_DA2P") (pintype "bidirectional"))
    )
    (net (code "85") (name "CAM7_D0_N") (class "Default")
      (node (ref "CON7") (pin "CAM_D0_N") (pinfunction "CAM_DN0_CAM_D0_N") (pintype "bidirectional"))
      (node (ref "M4") (pin "CLKAN") (pinfunction "CLKA_N_CLKAN") (pintype "bidirectional"))
    )
    (net (code "86") (name "CAM7_D0_P") (class "Default")
      (node (ref "CON7") (pin "CAM_D0_P") (pinfunction "CAM_DP0_CAM_D0_P") (pintype "bidirectional"))
      (node (ref "M4") (pin "CLKAP") (pinfunction "CLKA_P_CLKAP") (pintype "bidirectional"))
    )
    (net (code "87") (name "CAM7_D1_N") (class "Default")
      (node (ref "CON7") (pin "CAM_D1_N") (pinfunction "CAM_DN1_CAM_D1_N") (pintype "bidirectional"))
      (node (ref "M4") (pin "DA1N") (pinfunction "DA1_N_DA1N") (pintype "bidirectional"))
    )
    (net (code "88") (name "CAM7_D1_P") (class "Default")
      (node (ref "CON7") (pin "CAM_D1_P") (pinfunction "CAM_DP1_CAM_D1_P") (pintype "bidirectional"))
      (node (ref "M4") (pin "DA1P") (pinfunction "DA1_P_DA1P") (pintype "bidirectional"))
    )
    (net (code "89") (name "CAM8_C_N") (class "Default")
      (node (ref "CON8") (pin "CAM_C_N") (pinfunction "CAM_CN_CAM_C_N") (pintype "bidirectional"))
      (node (ref "M4") (pin "DB2N") (pinfunction "DB2_N_DB2N") (pintype "bidirectional"))
    )
    (net (code "90") (name "CAM8_C_P") (class "Default")
      (node (ref "CON8") (pin "CAM_C_P") (pinfunction "CAM_CP_CAM_C_P") (pintype "bidirectional"))
      (node (ref "M4") (pin "DB2P") (pinfunction "DB2_P_DB2P") (pintype "bidirectional"))
    )
    (net (code "91") (name "CAM8_D0_N") (class "Default")
      (node (ref "CON8") (pin "CAM_D0_N") (pinfunction "CAM_DN0_CAM_D0_N") (pintype "bidirectional"))
      (node (ref "M4") (pin "CLKBN") (pinfunction "CLKB_N_CLKBN") (pintype "bidirectional"))
    )
    (net (code "92") (name "CAM8_D0_P") (class "Default")
      (node (ref "CON8") (pin "CAM_D0_P") (pinfunction "CAM_DP0_CAM_D0_P") (pintype "bidirectional"))
      (node (ref "M4") (pin "CLKBP") (pinfunction "CLKB_P_CLKBP") (pintype "bidirectional"))
    )
    (net (code "93") (name "CAM8_D1_N") (class "Default")
      (node (ref "CON8") (pin "CAM_D1_N") (pinfunction "CAM_DN1_CAM_D1_N") (pintype "bidirectional"))
      (node (ref "M4") (pin "DB1N") (pinfunction "DB1_N_DB1N") (pintype "bidirectional"))
    )
    (net (code "94") (name "CAM8_D1_P") (class "Default")
      (node (ref "CON8") (pin "CAM_D1_P") (pinfunction "CAM_DP1_CAM_D1_P") (pintype "bidirectional"))
      (node (ref "M4") (pin "DB1P") (pinfunction "DB1_P_DB1P") (pintype "bidirectional"))
    )
    (net (code "95") (name "CAM_CLK") (class "Default")
      (node (ref "CON1") (pin "CAM_CLK") (pinfunction "CAM_CLK_CAM_CLK") (pintype "bidirectional"))
      (node (ref "CON2") (pin "CAM_CLK") (pinfunction "CAM_CLK_CAM_CLK") (pintype "bidirectional"))
      (node (ref "CON3") (pin "CAM_CLK") (pinfunction "CAM_CLK_CAM_CLK") (pintype "bidirectional"))
      (node (ref "CON4") (pin "CAM_CLK") (pinfunction "CAM_CLK_CAM_CLK") (pintype "bidirectional"))
      (node (ref "CON5") (pin "CAM_CLK") (pinfunction "CAM_CLK_CAM_CLK") (pintype "bidirectional"))
      (node (ref "CON6") (pin "CAM_CLK") (pinfunction "CAM_CLK_CAM_CLK") (pintype "bidirectional"))
      (node (ref "CON7") (pin "CAM_CLK") (pinfunction "CAM_CLK_CAM_CLK") (pintype "bidirectional"))
      (node (ref "CON8") (pin "CAM_CLK") (pinfunction "CAM_CLK_CAM_CLK") (pintype "bidirectional"))
      (node (ref "CON9") (pin "CAM_CLK") (pinfunction "CAM_CLK_CAM_CLK") (pintype "bidirectional"))
    )
    (net (code "96") (name "CAM_C_N") (class "Default")
      (node (ref "CON9") (pin "CAM_C_N") (pinfunction "CAM_CN_CAM_C_N") (pintype "bidirectional"))
      (node (ref "M7") (pin "D2N") (pinfunction "D2OUT_N_D2N") (pintype "bidirectional"))
    )
    (net (code "97") (name "CAM_C_P") (class "Default")
      (node (ref "CON9") (pin "CAM_C_P") (pinfunction "CAM_CP_CAM_C_P") (pintype "bidirectional"))
      (node (ref "M7") (pin "D2P") (pinfunction "D2OUT_P_D2P") (pintype "bidirectional"))
    )
    (net (code "98") (name "CAM_D0_N") (class "Default")
      (node (ref "CON9") (pin "CAM_D0_N") (pinfunction "CAM_DN0_CAM_D0_N") (pintype "bidirectional"))
      (node (ref "M7") (pin "CLKN") (pinfunction "CLKOUT_N_CLKN") (pintype "bidirectional"))
    )
    (net (code "99") (name "CAM_D0_P") (class "Default")
      (node (ref "CON9") (pin "CAM_D0_P") (pinfunction "CAM_DP0_CAM_D0_P") (pintype "bidirectional"))
      (node (ref "M7") (pin "CLKP") (pinfunction "CLKOUT_P_CLKP") (pintype "bidirectional"))
    )
    (net (code "100") (name "CAM_D1_N") (class "Default")
      (node (ref "CON9") (pin "CAM_D1_N") (pinfunction "CAM_DN1_CAM_D1_N") (pintype "bidirectional"))
      (node (ref "M7") (pin "D1N") (pinfunction "D1OUT_N_D1N") (pintype "bidirectional"))
    )
    (net (code "101") (name "CAM_D1_P") (class "Default")
      (node (ref "CON9") (pin "CAM_D1_P") (pinfunction "CAM_DP1_CAM_D1_P") (pintype "bidirectional"))
      (node (ref "M7") (pin "D1P") (pinfunction "D1OUT_P_D1P") (pintype "bidirectional"))
    )
    (net (code "102") (name "CAM_GPIO") (class "Default")
      (node (ref "CON1") (pin "CAM_GPIO") (pinfunction "CAM_GPIO_CAM_GPIO") (pintype "bidirectional"))
      (node (ref "CON2") (pin "CAM_GPIO") (pinfunction "CAM_GPIO_CAM_GPIO") (pintype "bidirectional"))
      (node (ref "CON3") (pin "CAM_GPIO") (pinfunction "CAM_GPIO_CAM_GPIO") (pintype "bidirectional"))
      (node (ref "CON4") (pin "CAM_GPIO") (pinfunction "CAM_GPIO_CAM_GPIO") (pintype "bidirectional"))
      (node (ref "CON5") (pin "CAM_GPIO") (pinfunction "CAM_GPIO_CAM_GPIO") (pintype "bidirectional"))
      (node (ref "CON6") (pin "CAM_GPIO") (pinfunction "CAM_GPIO_CAM_GPIO") (pintype "bidirectional"))
      (node (ref "CON7") (pin "CAM_GPIO") (pinfunction "CAM_GPIO_CAM_GPIO") (pintype "bidirectional"))
      (node (ref "CON8") (pin "CAM_GPIO") (pinfunction "CAM_GPIO_CAM_GPIO") (pintype "bidirectional"))
      (node (ref "CON9") (pin "CAM_GPIO") (pinfunction "CAM_GPIO_CAM_GPIO") (pintype "bidirectional"))
    )
    (net (code "103") (name "D2") (class "Default")
      (node (ref "PI") (pin "33") (pinfunction "GPIO13_33_33") (pintype "bidirectional"))
      (node (ref "U1") (pin "32") (pinfunction "PD2_32") (pintype "bidirectional"))
    )
    (net (code "104") (name "D3") (class "Default")
      (node (ref "PI") (pin "31") (pinfunction "GPIO06_31_31") (pintype "bidirectional"))
      (node (ref "U1") (pin "1") (pinfunction "PD3_1") (pintype "bidirectional"))
    )
    (net (code "105") (name "D4") (class "Default")
      (node (ref "PI") (pin "29") (pinfunction "GPIO05_29_29") (pintype "bidirectional"))
      (node (ref "U1") (pin "2") (pinfunction "PD4_2") (pintype "bidirectional"))
    )
    (net (code "106") (name "D8") (class "Default")
      (node (ref "Q1") (pin "1") (pinfunction "G_1") (pintype "bidirectional"))
      (node (ref "U1") (pin "12") (pinfunction "PB0_12") (pintype "bidirectional"))
    )
    (net (code "107") (name "GND") (class "Default")
      (node (ref "C1") (pin "2") (pinfunction "2_2") (pintype "passive"))
      (node (ref "C10") (pin "2") (pinfunction "2_2") (pintype "passive"))
      (node (ref "C11") (pin "2") (pinfunction "2_2") (pintype "passive"))
      (node (ref "C12") (pin "2") (pinfunction "2_2") (pintype "passive"))
      (node (ref "C13") (pin "2") (pinfunction "2_2") (pintype "passive"))
      (node (ref "C14") (pin "2") (pinfunction "2_2") (pintype "passive"))
      (node (ref "C15") (pin "2") (pinfunction "2_2") (pintype "passive"))
      (node (ref "C16") (pin "2") (pinfunction "2_2") (pintype "passive"))
      (node (ref "C17") (pin "2") (pinfunction "2_2") (pintype "passive"))
      (node (ref "C18") (pin "2") (pinfunction "2_2") (pintype "passive"))
      (node (ref "C19") (pin "2") (pinfunction "2_2") (pintype "passive"))
      (node (ref "C2") (pin "2") (pinfunction "2_2") (pintype "passive"))
      (node (ref "C21") (pin "2") (pinfunction "2_2") (pintype "passive"))
      (node (ref "C4") (pin "2") (pinfunction "2_2") (pintype "passive"))
      (node (ref "C6") (pin "2") (pinfunction "2_2") (pintype "passive"))
      (node (ref "C7") (pin "2") (pinfunction "2_2") (pintype "passive"))
      (node (ref "C8") (pin "2") (pinfunction "2_2") (pintype "passive"))
      (node (ref "C9") (pin "2") (pinfunction "2_2") (pintype "passive"))
      (node (ref "CON1") (pin "GND") (pinfunction "GND0_GND") (pintype "bidirectional"))
      (node (ref "CON1") (pin "GND1") (pinfunction "GND1_GND1") (pintype "bidirectional"))
      (node (ref "CON1") (pin "GND2") (pinfunction "GND2_GND2") (pintype "bidirectional"))
      (node (ref "CON1") (pin "GND3") (pinfunction "GND3_GND3") (pintype "bidirectional"))
      (node (ref "CON2") (pin "GND") (pinfunction "GND0_GND") (pintype "bidirectional"))
      (node (ref "CON2") (pin "GND1") (pinfunction "GND1_GND1") (pintype "bidirectional"))
      (node (ref "CON2") (pin "GND2") (pinfunction "GND2_GND2") (pintype "bidirectional"))
      (node (ref "CON2") (pin "GND3") (pinfunction "GND3_GND3") (pintype "bidirectional"))
      (node (ref "CON3") (pin "GND") (pinfunction "GND0_GND") (pintype "bidirectional"))
      (node (ref "CON3") (pin "GND1") (pinfunction "GND1_GND1") (pintype "bidirectional"))
      (node (ref "CON3") (pin "GND2") (pinfunction "GND2_GND2") (pintype "bidirectional"))
      (node (ref "CON3") (pin "GND3") (pinfunction "GND3_GND3") (pintype "bidirectional"))
      (node (ref "CON4") (pin "GND") (pinfunction "GND0_GND") (pintype "bidirectional"))
      (node (ref "CON4") (pin "GND1") (pinfunction "GND1_GND1") (pintype "bidirectional"))
      (node (ref "CON4") (pin "GND2") (pinfunction "GND2_GND2") (pintype "bidirectional"))
      (node (ref "CON4") (pin "GND3") (pinfunction "GND3_GND3") (pintype "bidirectional"))
      (node (ref "CON5") (pin "GND") (pinfunction "GND0_GND") (pintype "bidirectional"))
      (node (ref "CON5") (pin "GND1") (pinfunction "GND1_GND1") (pintype "bidirectional"))
      (node (ref "CON5") (pin "GND2") (pinfunction "GND2_GND2") (pintype "bidirectional"))
      (node (ref "CON5") (pin "GND3") (pinfunction "GND3_GND3") (pintype "bidirectional"))
      (node (ref "CON6") (pin "GND") (pinfunction "GND0_GND") (pintype "bidirectional"))
      (node (ref "CON6") (pin "GND1") (pinfunction "GND1_GND1") (pintype "bidirectional"))
      (node (ref "CON6") (pin "GND2") (pinfunction "GND2_GND2") (pintype "bidirectional"))
      (node (ref "CON6") (pin "GND3") (pinfunction "GND3_GND3") (pintype "bidirectional"))
      (node (ref "CON7") (pin "GND") (pinfunction "GND0_GND") (pintype "bidirectional"))
      (node (ref "CON7") (pin "GND1") (pinfunction "GND1_GND1") (pintype "bidirectional"))
      (node (ref "CON7") (pin "GND2") (pinfunction "GND2_GND2") (pintype "bidirectional"))
      (node (ref "CON7") (pin "GND3") (pinfunction "GND3_GND3") (pintype "bidirectional"))
      (node (ref "CON8") (pin "GND") (pinfunction "GND0_GND") (pintype "bidirectional"))
      (node (ref "CON8") (pin "GND1") (pinfunction "GND1_GND1") (pintype "bidirectional"))
      (node (ref "CON8") (pin "GND2") (pinfunction "GND2_GND2") (pintype "bidirectional"))
      (node (ref "CON8") (pin "GND3") (pinfunction "GND3_GND3") (pintype "bidirectional"))
      (node (ref "CON9") (pin "GND") (pinfunction "GND0_GND") (pintype "bidirectional"))
      (node (ref "CON9") (pin "GND1") (pinfunction "GND1_GND1") (pintype "bidirectional"))
      (node (ref "CON9") (pin "GND2") (pinfunction "GND2_GND2") (pintype "bidirectional"))
      (node (ref "CON9") (pin "GND3") (pinfunction "GND3_GND3") (pintype "bidirectional"))
      (node (ref "ISP1") (pin "6") (pinfunction "GND_6") (pintype "power_in"))
      (node (ref "J2") (pin "3") (pinfunction "S_3") (pintype "passive"))
      (node (ref "J2") (pin "4") (pinfunction "S_4") (pintype "passive"))
      (node (ref "M1") (pin "/OE") (pinfunction "/OE_/OE") (pintype "bidirectional"))
      (node (ref "M1") (pin "GND") (pinfunction "GND_GND") (pintype "bidirectional"))
      (node (ref "M2") (pin "/OE") (pinfunction "/OE_/OE") (pintype "bidirectional"))
      (node (ref "M2") (pin "GND") (pinfunction "GND_GND") (pintype "bidirectional"))
      (node (ref "M3") (pin "/OE") (pinfunction "/OE_/OE") (pintype "bidirectional"))
      (node (ref "M3") (pin "GND") (pinfunction "GND_GND") (pintype "bidirectional"))
      (node (ref "M4") (pin "/OE") (pinfunction "/OE_/OE") (pintype "bidirectional"))
      (node (ref "M4") (pin "GND") (pinfunction "GND_GND") (pintype "bidirectional"))
      (node (ref "M5") (pin "/OE") (pinfunction "/OE_/OE") (pintype "bidirectional"))
      (node (ref "M5") (pin "GND") (pinfunction "GND_GND") (pintype "bidirectional"))
      (node (ref "M6") (pin "/OE") (pinfunction "/OE_/OE") (pintype "bidirectional"))
      (node (ref "M6") (pin "GND") (pinfunction "GND_GND") (pintype "bidirectional"))
      (node (ref "M7") (pin "/OE") (pinfunction "/OE_/OE") (pintype "bidirectional"))
      (node (ref "M7") (pin "GND") (pinfunction "GND_GND") (pintype "bidirectional"))
      (node (ref "PI") (pin "06") (pinfunction "GND_06_06") (pintype "bidirectional"))
      (node (ref "PI") (pin "09") (pinfunction "GND_09_09") (pintype "bidirectional"))
      (node (ref "PI") (pin "14") (pinfunction "GND_14_14") (pintype "bidirectional"))
      (node (ref "PI") (pin "20") (pinfunction "GND_20_20") (pintype "bidirectional"))
      (node (ref "PI") (pin "25") (pinfunction "GND_25_25") (pintype "bidirectional"))
      (node (ref "PI") (pin "30") (pinfunction "GND_30_30") (pintype "bidirectional"))
      (node (ref "PI") (pin "34") (pinfunction "GND_34_34") (pintype "bidirectional"))
      (node (ref "PI") (pin "39") (pinfunction "GND_39_39") (pintype "bidirectional"))
      (node (ref "Q1") (pin "3") (pinfunction "D_3") (pintype "bidirectional"))
      (node (ref "RT1") (pin "5") (pinfunction "GND_5") (pintype "power_in"))
      (node (ref "S1") (pin "VSS") (pinfunction "VSS_VSS") (pintype "power_in"))
      (node (ref "SW1") (pin "2") (pinfunction "S_2") (pintype "passive"))
      (node (ref "SW1") (pin "4") (pinfunction "S1_4") (pintype "passive"))
      (node (ref "U$2") (pin "GND") (pinfunction "GND_GND") (pintype "bidirectional"))
      (node (ref "U1") (pin "21") (pinfunction "GND_21") (pintype "passive"))
      (node (ref "U1") (pin "3") (pinfunction "GND_2_3") (pintype "passive"))
      (node (ref "U1") (pin "5") (pinfunction "GND_3_5") (pintype "passive"))
      (node (ref "X1") (pin "COM") (pinfunction "COM_COM") (pintype "bidirectional"))
    )
    (net (code "108") (name "MISO") (class "Default")
      (node (ref "ISP1") (pin "1") (pinfunction "MISO_1") (pintype "input"))
      (node (ref "U1") (pin "16") (pinfunction "PB4_16") (pintype "bidirectional"))
    )
    (net (code "109") (name "MOSI") (class "Default")
      (node (ref "ISP1") (pin "4") (pinfunction "MOSI_4") (pintype "output"))
      (node (ref "U1") (pin "15") (pinfunction "PB3_15") (pintype "bidirectional"))
    )
    (net (code "110") (name "Net-(J1A-S)") (class "Default")
      (node (ref "J1") (pin "1") (pinfunction "S_1") (pintype "passive"))
      (node (ref "PI") (pin "08") (pinfunction "TXD0_GPIO14_08_08") (pintype "bidirectional"))
    )
    (net (code "111") (name "Net-(J1B-S)") (class "Default")
      (node (ref "J1") (pin "2") (pinfunction "S_2") (pintype "passive"))
      (node (ref "PI") (pin "10") (pinfunction "RXD0_GPIO15_10_10") (pintype "bidirectional"))
    )
    (net (code "112") (name "Net-(J3C-S)") (class "Default")
      (node (ref "J3") (pin "3") (pinfunction "S_3") (pintype "passive"))
      (node (ref "Q1") (pin "2") (pinfunction "S_2") (pintype "bidirectional"))
    )
    (net (code "113") (name "Net-(PI-3.3V_01)") (class "Default")
      (node (ref "PI") (pin "01") (pinfunction "3.3V_01_01") (pintype "bidirectional"))
      (node (ref "RT1") (pin "2") (pinfunction "VCC_2") (pintype "power_in"))
    )
    (net (code "114") (name "Net-(PI-GPIO02_SDA1_03)") (class "Default")
      (node (ref "PI") (pin "03") (pinfunction "GPIO02_SDA1_03_03") (pintype "bidirectional"))
      (node (ref "RT1") (pin "7") (pinfunction "SDA_7") (pintype "bidirectional"))
    )
    (net (code "115") (name "Net-(PI-GPIO03_SCL1_05)") (class "Default")
      (node (ref "PI") (pin "05") (pinfunction "GPIO03_SCL1_05_05") (pintype "bidirectional"))
      (node (ref "RT1") (pin "8") (pinfunction "SCL_8") (pintype "bidirectional"))
    )
    (net (code "116") (name "Net-(U1-AREF)") (class "Default")
      (node (ref "C19") (pin "1") (pinfunction "1_1") (pintype "passive"))
      (node (ref "U1") (pin "20") (pinfunction "AREF_20") (pintype "input"))
    )
    (net (code "117") (name "Net-(U1-PD5)") (class "Default")
      (node (ref "SJ1") (pin "3") (pinfunction "3_3") (pintype "passive"))
      (node (ref "U1") (pin "9") (pinfunction "PD5_9") (pintype "bidirectional"))
    )
    (net (code "118") (name "Net-(U1-PD6)") (class "Default")
      (node (ref "SJ2") (pin "3") (pinfunction "3_3") (pintype "passive"))
      (node (ref "U1") (pin "10") (pinfunction "PD6_10") (pintype "bidirectional"))
    )
    (net (code "119") (name "Net-(U1-PD7)") (class "Default")
      (node (ref "SJ3") (pin "3") (pinfunction "3_3") (pintype "passive"))
      (node (ref "U1") (pin "11") (pinfunction "PD7_11") (pintype "bidirectional"))
    )
    (net (code "120") (name "PWM") (class "Default")
      (node (ref "J3") (pin "1") (pinfunction "S_1") (pintype "passive"))
      (node (ref "U1") (pin "13") (pinfunction "PB1_13") (pintype "bidirectional"))
    )
    (net (code "121") (name "RESET") (class "Default")
      (node (ref "ISP1") (pin "5") (pinfunction "RST_5") (pintype "output"))
      (node (ref "R1") (pin "1") (pinfunction "1_1") (pintype "passive"))
      (node (ref "SW1") (pin "1") (pinfunction "P_1") (pintype "passive"))
      (node (ref "SW1") (pin "3") (pinfunction "P1_3") (pintype "passive"))
      (node (ref "U1") (pin "29") (pinfunction "PC6_29") (pintype "bidirectional"))
    )
    (net (code "122") (name "RX") (class "Default")
      (node (ref "U1") (pin "30") (pinfunction "PD0_30") (pintype "bidirectional"))
    )
    (net (code "123") (name "SCK") (class "Default")
      (node (ref "ISP1") (pin "3") (pinfunction "SCK_3") (pintype "output"))
      (node (ref "U1") (pin "17") (pinfunction "PB5_17") (pintype "bidirectional"))
    )
    (net (code "124") (name "SCL") (class "Default")
      (node (ref "CON1") (pin "SCL") (pinfunction "SCL_SCL") (pintype "bidirectional"))
      (node (ref "CON2") (pin "SCL") (pinfunction "SCL_SCL") (pintype "bidirectional"))
      (node (ref "CON3") (pin "SCL") (pinfunction "SCL_SCL") (pintype "bidirectional"))
      (node (ref "CON4") (pin "SCL") (pinfunction "SCL_SCL") (pintype "bidirectional"))
      (node (ref "CON5") (pin "SCL") (pinfunction "SCL_SCL") (pintype "bidirectional"))
      (node (ref "CON6") (pin "SCL") (pinfunction "SCL_SCL") (pintype "bidirectional"))
      (node (ref "CON7") (pin "SCL") (pinfunction "SCL_SCL") (pintype "bidirectional"))
      (node (ref "CON8") (pin "SCL") (pinfunction "SCL_SCL") (pintype "bidirectional"))
      (node (ref "CON9") (pin "SCL") (pinfunction "SCL_SCL") (pintype "bidirectional"))
    )
    (net (code "125") (name "SDA") (class "Default")
      (node (ref "CON1") (pin "SDA") (pinfunction "SDA_SDA") (pintype "bidirectional"))
      (node (ref "CON2") (pin "SDA") (pinfunction "SDA_SDA") (pintype "bidirectional"))
      (node (ref "CON3") (pin "SDA") (pinfunction "SDA_SDA") (pintype "bidirectional"))
      (node (ref "CON4") (pin "SDA") (pinfunction "SDA_SDA") (pintype "bidirectional"))
      (node (ref "CON5") (pin "SDA") (pinfunction "SDA_SDA") (pintype "bidirectional"))
      (node (ref "CON6") (pin "SDA") (pinfunction "SDA_SDA") (pintype "bidirectional"))
      (node (ref "CON7") (pin "SDA") (pinfunction "SDA_SDA") (pintype "bidirectional"))
      (node (ref "CON8") (pin "SDA") (pinfunction "SDA_SDA") (pintype "bidirectional"))
      (node (ref "CON9") (pin "SDA") (pinfunction "SDA_SDA") (pintype "bidirectional"))
    )
    (net (code "126") (name "SEL1") (class "Default")
      (node (ref "M1") (pin "SEL") (pinfunction "SEL_SEL") (pintype "bidirectional"))
      (node (ref "M2") (pin "SEL") (pinfunction "SEL_SEL") (pintype "bidirectional"))
      (node (ref "M3") (pin "SEL") (pinfunction "SEL_SEL") (pintype "bidirectional"))
      (node (ref "M4") (pin "SEL") (pinfunction "SEL_SEL") (pintype "bidirectional"))
      (node (ref "SJ1") (pin "2") (pinfunction "2_2") (pintype "passive"))
    )
    (net (code "127") (name "SEL1_PI") (class "Default")
      (node (ref "PI") (pin "11") (pinfunction "GPIO17_GEN0_11_11") (pintype "bidirectional"))
      (node (ref "SJ1") (pin "1") (pinfunction "1_1") (pintype "passive"))
    )
    (net (code "128") (name "SEL2") (class "Default")
      (node (ref "M5") (pin "SEL") (pinfunction "SEL_SEL") (pintype "bidirectional"))
      (node (ref "M6") (pin "SEL") (pinfunction "SEL_SEL") (pintype "bidirectional"))
      (node (ref "SJ2") (pin "2") (pinfunction "2_2") (pintype "passive"))
    )
    (net (code "129") (name "SEL2_PI") (class "Default")
      (node (ref "PI") (pin "13") (pinfunction "GPIO27_GEN2_13_13") (pintype "bidirectional"))
      (node (ref "SJ2") (pin "1") (pinfunction "1_1") (pintype "passive"))
    )
    (net (code "130") (name "SEL3") (class "Default")
      (node (ref "M7") (pin "SEL") (pinfunction "SEL_SEL") (pintype "bidirectional"))
      (node (ref "SJ3") (pin "2") (pinfunction "2_2") (pintype "passive"))
    )
    (net (code "131") (name "SEL3_PI") (class "Default")
      (node (ref "PI") (pin "15") (pinfunction "GPIO22_GEN3_15_15") (pintype "bidirectional"))
      (node (ref "SJ3") (pin "1") (pinfunction "1_1") (pintype "passive"))
    )
    (net (code "132") (name "TX") (class "Default")
      (node (ref "U1") (pin "31") (pinfunction "PD1_31") (pintype "bidirectional"))
    )
    (net (code "133") (name "VBAT") (class "Default")
      (node (ref "C21") (pin "1") (pinfunction "1_1") (pintype "passive"))
      (node (ref "RT1") (pin "6") (pinfunction "VBAT_6") (pintype "power_in"))
      (node (ref "S1") (pin "VDD") (pinfunction "VDD_VDD") (pintype "power_in"))
    )
    (net (code "134") (name "XTAL1") (class "Default")
      (node (ref "U1") (pin "7") (pinfunction "PB6_7") (pintype "bidirectional"))
      (node (ref "X1") (pin "XTAL1") (pinfunction "XTAL1_XTAL1") (pintype "bidirectional"))
    )
    (net (code "135") (name "XTAL2") (class "Default")
      (node (ref "U1") (pin "8") (pinfunction "PB7_8") (pintype "bidirectional"))
      (node (ref "X1") (pin "XTAL2") (pinfunction "XTAL2_XTAL2") (pintype "bidirectional"))
    )
    (net (code "136") (name "unconnected-(CON9-+3V3-Pad3.3V)") (class "Default")
      (node (ref "CON9") (pin "3.3V") (pinfunction "+3V3_3.3V") (pintype "bidirectional"))
    )
    (net (code "137") (name "unconnected-(PI-3.3V_17-Pad17)") (class "Default")
      (node (ref "PI") (pin "17") (pinfunction "3.3V_17_17") (pintype "bidirectional"))
    )
    (net (code "138") (name "unconnected-(PI-GEN1_GPIO18_12-Pad12)") (class "Default")
      (node (ref "PI") (pin "12") (pinfunction "GEN1_GPIO18_12_12") (pintype "bidirectional"))
    )
    (net (code "139") (name "unconnected-(PI-GEN4_GPIO23_16-Pad16)") (class "Default")
      (node (ref "PI") (pin "16") (pinfunction "GEN4_GPIO23_16_16") (pintype "bidirectional"))
    )
    (net (code "140") (name "unconnected-(PI-GEN5_GPIO24_18-Pad18)") (class "Default")
      (node (ref "PI") (pin "18") (pinfunction "GEN5_GPIO24_18_18") (pintype "bidirectional"))
    )
    (net (code "141") (name "unconnected-(PI-GEN6_GPIO25_22-Pad22)") (class "Default")
      (node (ref "PI") (pin "22") (pinfunction "GEN6_GPIO25_22_22") (pintype "bidirectional"))
    )
    (net (code "142") (name "unconnected-(PI-GPIO04_GCLK_07-Pad07)") (class "Default")
      (node (ref "PI") (pin "07") (pinfunction "GPIO04_GCLK_07_07") (pintype "bidirectional"))
    )
    (net (code "143") (name "unconnected-(PI-GPIO09_SPIMISO_21-Pad21)") (class "Default")
      (node (ref "PI") (pin "21") (pinfunction "GPIO09_SPIMISO_21_21") (pintype "bidirectional"))
    )
    (net (code "144") (name "unconnected-(PI-GPIO10_SPIMOSI_19-Pad19)") (class "Default")
      (node (ref "PI") (pin "19") (pinfunction "GPIO10_SPIMOSI_19_19") (pintype "bidirectional"))
    )
    (net (code "145") (name "unconnected-(PI-GPIO11_SPICLK_23-Pad23)") (class "Default")
      (node (ref "PI") (pin "23") (pinfunction "GPIO11_SPICLK_23_23") (pintype "bidirectional"))
    )
    (net (code "146") (name "unconnected-(PI-GPIO12_32-Pad32)") (class "Default")
      (node (ref "PI") (pin "32") (pinfunction "GPIO12_32_32") (pintype "bidirectional"))
    )
    (net (code "147") (name "unconnected-(PI-GPIO16_36-Pad36)") (class "Default")
      (node (ref "PI") (pin "36") (pinfunction "GPIO16_36_36") (pintype "bidirectional"))
    )
    (net (code "148") (name "unconnected-(PI-I2C_IDSC_28-Pad28)") (class "Default")
      (node (ref "PI") (pin "28") (pinfunction "I2C_IDSC_28_28") (pintype "bidirectional"))
    )
    (net (code "149") (name "unconnected-(PI-IDSD_I2C_27-Pad27)") (class "Default")
      (node (ref "PI") (pin "27") (pinfunction "IDSD_I2C_27_27") (pintype "bidirectional"))
    )
    (net (code "150") (name "unconnected-(PI-SPICE0N_GPIO08_24-Pad24)") (class "Default")
      (node (ref "PI") (pin "24") (pinfunction "SPICE0N_GPIO08_24_24") (pintype "bidirectional"))
    )
    (net (code "151") (name "unconnected-(PI-SPICE1N_GPIO07_26-Pad26)") (class "Default")
      (node (ref "PI") (pin "26") (pinfunction "SPICE1N_GPIO07_26_26") (pintype "bidirectional"))
    )
    (net (code "152") (name "unconnected-(RT1-32KHZ-Pad1)") (class "Default")
      (node (ref "RT1") (pin "1") (pinfunction "32KHZ_1") (pintype "output"))
    )
    (net (code "153") (name "unconnected-(RT1-{slash}INT-Pad3)") (class "Default")
      (node (ref "RT1") (pin "3") (pinfunction "/INT_3") (pintype "output"))
    )
    (net (code "154") (name "unconnected-(RT1-{slash}RST-Pad4)") (class "Default")
      (node (ref "RT1") (pin "4") (pinfunction "/RST_4") (pintype "input"))
    )
    (net (code "155") (name "unconnected-(U$2-Pad3V3)") (class "Default")
      (node (ref "U$2") (pin "3V3") (pinfunction "3V3_3V3") (pintype "bidirectional"))
    )
    (net (code "156") (name "unconnected-(U$2-PadRST)") (class "Default")
      (node (ref "U$2") (pin "RST") (pinfunction "RST_RST") (pintype "bidirectional"))
    )
    (net (code "157") (name "unconnected-(U1-ADC6-Pad19)") (class "Default")
      (node (ref "U1") (pin "19") (pinfunction "ADC6_19") (pintype "input"))
    )
    (net (code "158") (name "unconnected-(U1-ADC7-Pad22)") (class "Default")
      (node (ref "U1") (pin "22") (pinfunction "ADC7_22") (pintype "input"))
    )
    (net (code "159") (name "unconnected-(U1-PB2-Pad14)") (class "Default")
      (node (ref "U1") (pin "14") (pinfunction "PB2_14") (pintype "bidirectional"))
    )
  )
)
